# pca10100_sheet3_pin_map.net
KiCad netlist of a schematic drawn in Altium Designer
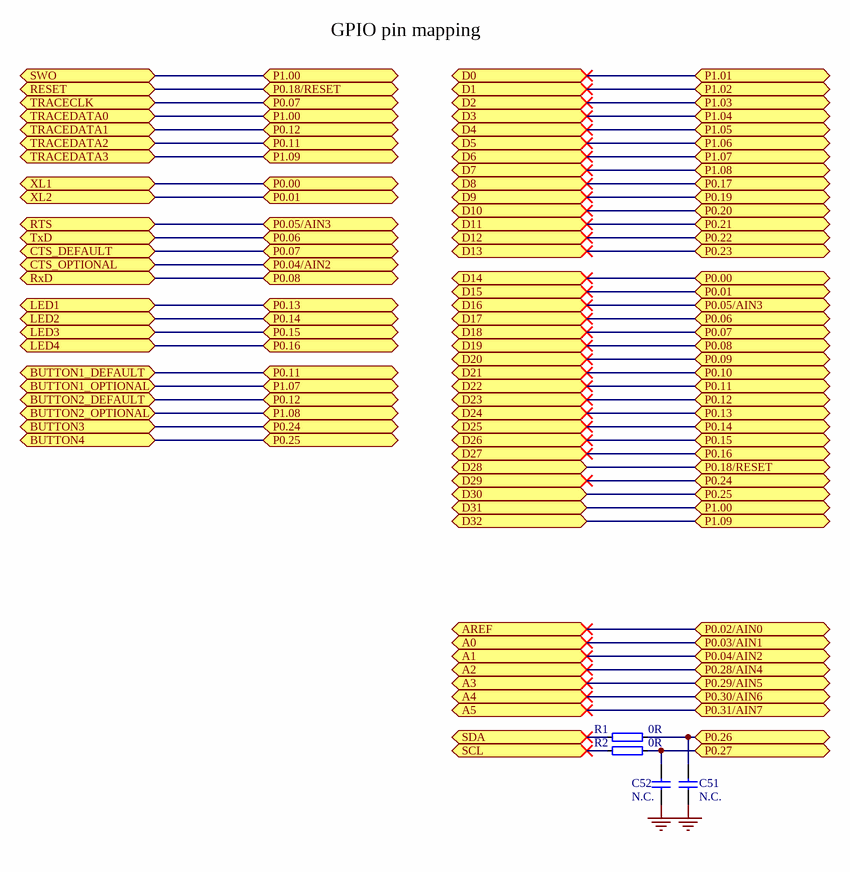
[diagram p0: pca10100_sheet3_pin_map.SchDoc]

(export (version "E")
  (design (tool "Eeschema 10.0.6"))
  (components
    (comp (ref "C51")
      (value "N.C.")
      (footprint "CAPC0603X03L_C")
      (description "Not mounted")
      (fields (field (name "PART NUMBER") "C0201-N.C.") (field (name "PUBLISHER") "Nordic Semiconductor"))
      (libsource (lib "Nordic Passive DB") (part "CAP"))
    )
    (comp (ref "C52")
      (value "N.C.")
      (footprint "CAPC0603X03L_C")
      (description "Not mounted")
      (fields (field (name "PART NUMBER") "C0201-N.C.") (field (name "PUBLISHER") "Nordic Semiconductor"))
      (libsource (lib "Nordic Passive DB") (part "CAP"))
    )
    (comp (ref "R1")
      (value "0R")
      (footprint "RESC0603X03L_C")
      (description "Resistor, ±5%, 0.05W")
      (fields (field (name "PART NUMBER") "R0201-0R") (field (name "PUBLISHER") "Nordic Semiconductor"))
      (libsource (lib "Nordic Passive DB") (part "RES_1"))
    )
    (comp (ref "R2")
      (value "0R")
      (footprint "RESC0603X03L_C")
      (description "Resistor, ±5%, 0.05W")
      (fields (field (name "PART NUMBER") "R0201-0R") (field (name "PUBLISHER") "Nordic Semiconductor"))
      (libsource (lib "Nordic Passive DB") (part "RES_1"))
    )
  )
  (nets
    (net (code "41") (name "/P0.26") (class "Default")
      (node (ref "C51") (pin "2") (pinfunction "2_2") (pintype "passive"))
      (node (ref "R1") (pin "2") (pinfunction "2_2") (pintype "passive"))
    )
    (net (code "42") (name "/P0.27") (class "Default")
      (node (ref "C52") (pin "1") (pinfunction "1_1") (pintype "passive"))
      (node (ref "R2") (pin "2") (pinfunction "2_2") (pintype "passive"))
    )
    (net (code "43") (name "/SCL") (class "Default")
      (node (ref "R2") (pin "1") (pinfunction "1_1") (pintype "passive+no_connect"))
    )
    (net (code "44") (name "/SDA") (class "Default")
      (node (ref "R1") (pin "1") (pinfunction "1_1") (pintype "passive+no_connect"))
    )
    (net (code "45") (name "GND") (class "Default")
      (node (ref "C51") (pin "1") (pinfunction "1_1") (pintype "passive"))
      (node (ref "C52") (pin "2") (pinfunction "2_2") (pintype "passive"))
    )
  )
)
